# M-LVDS_PHY.net
KiCad netlist of a schematic drawn in Altium Designer
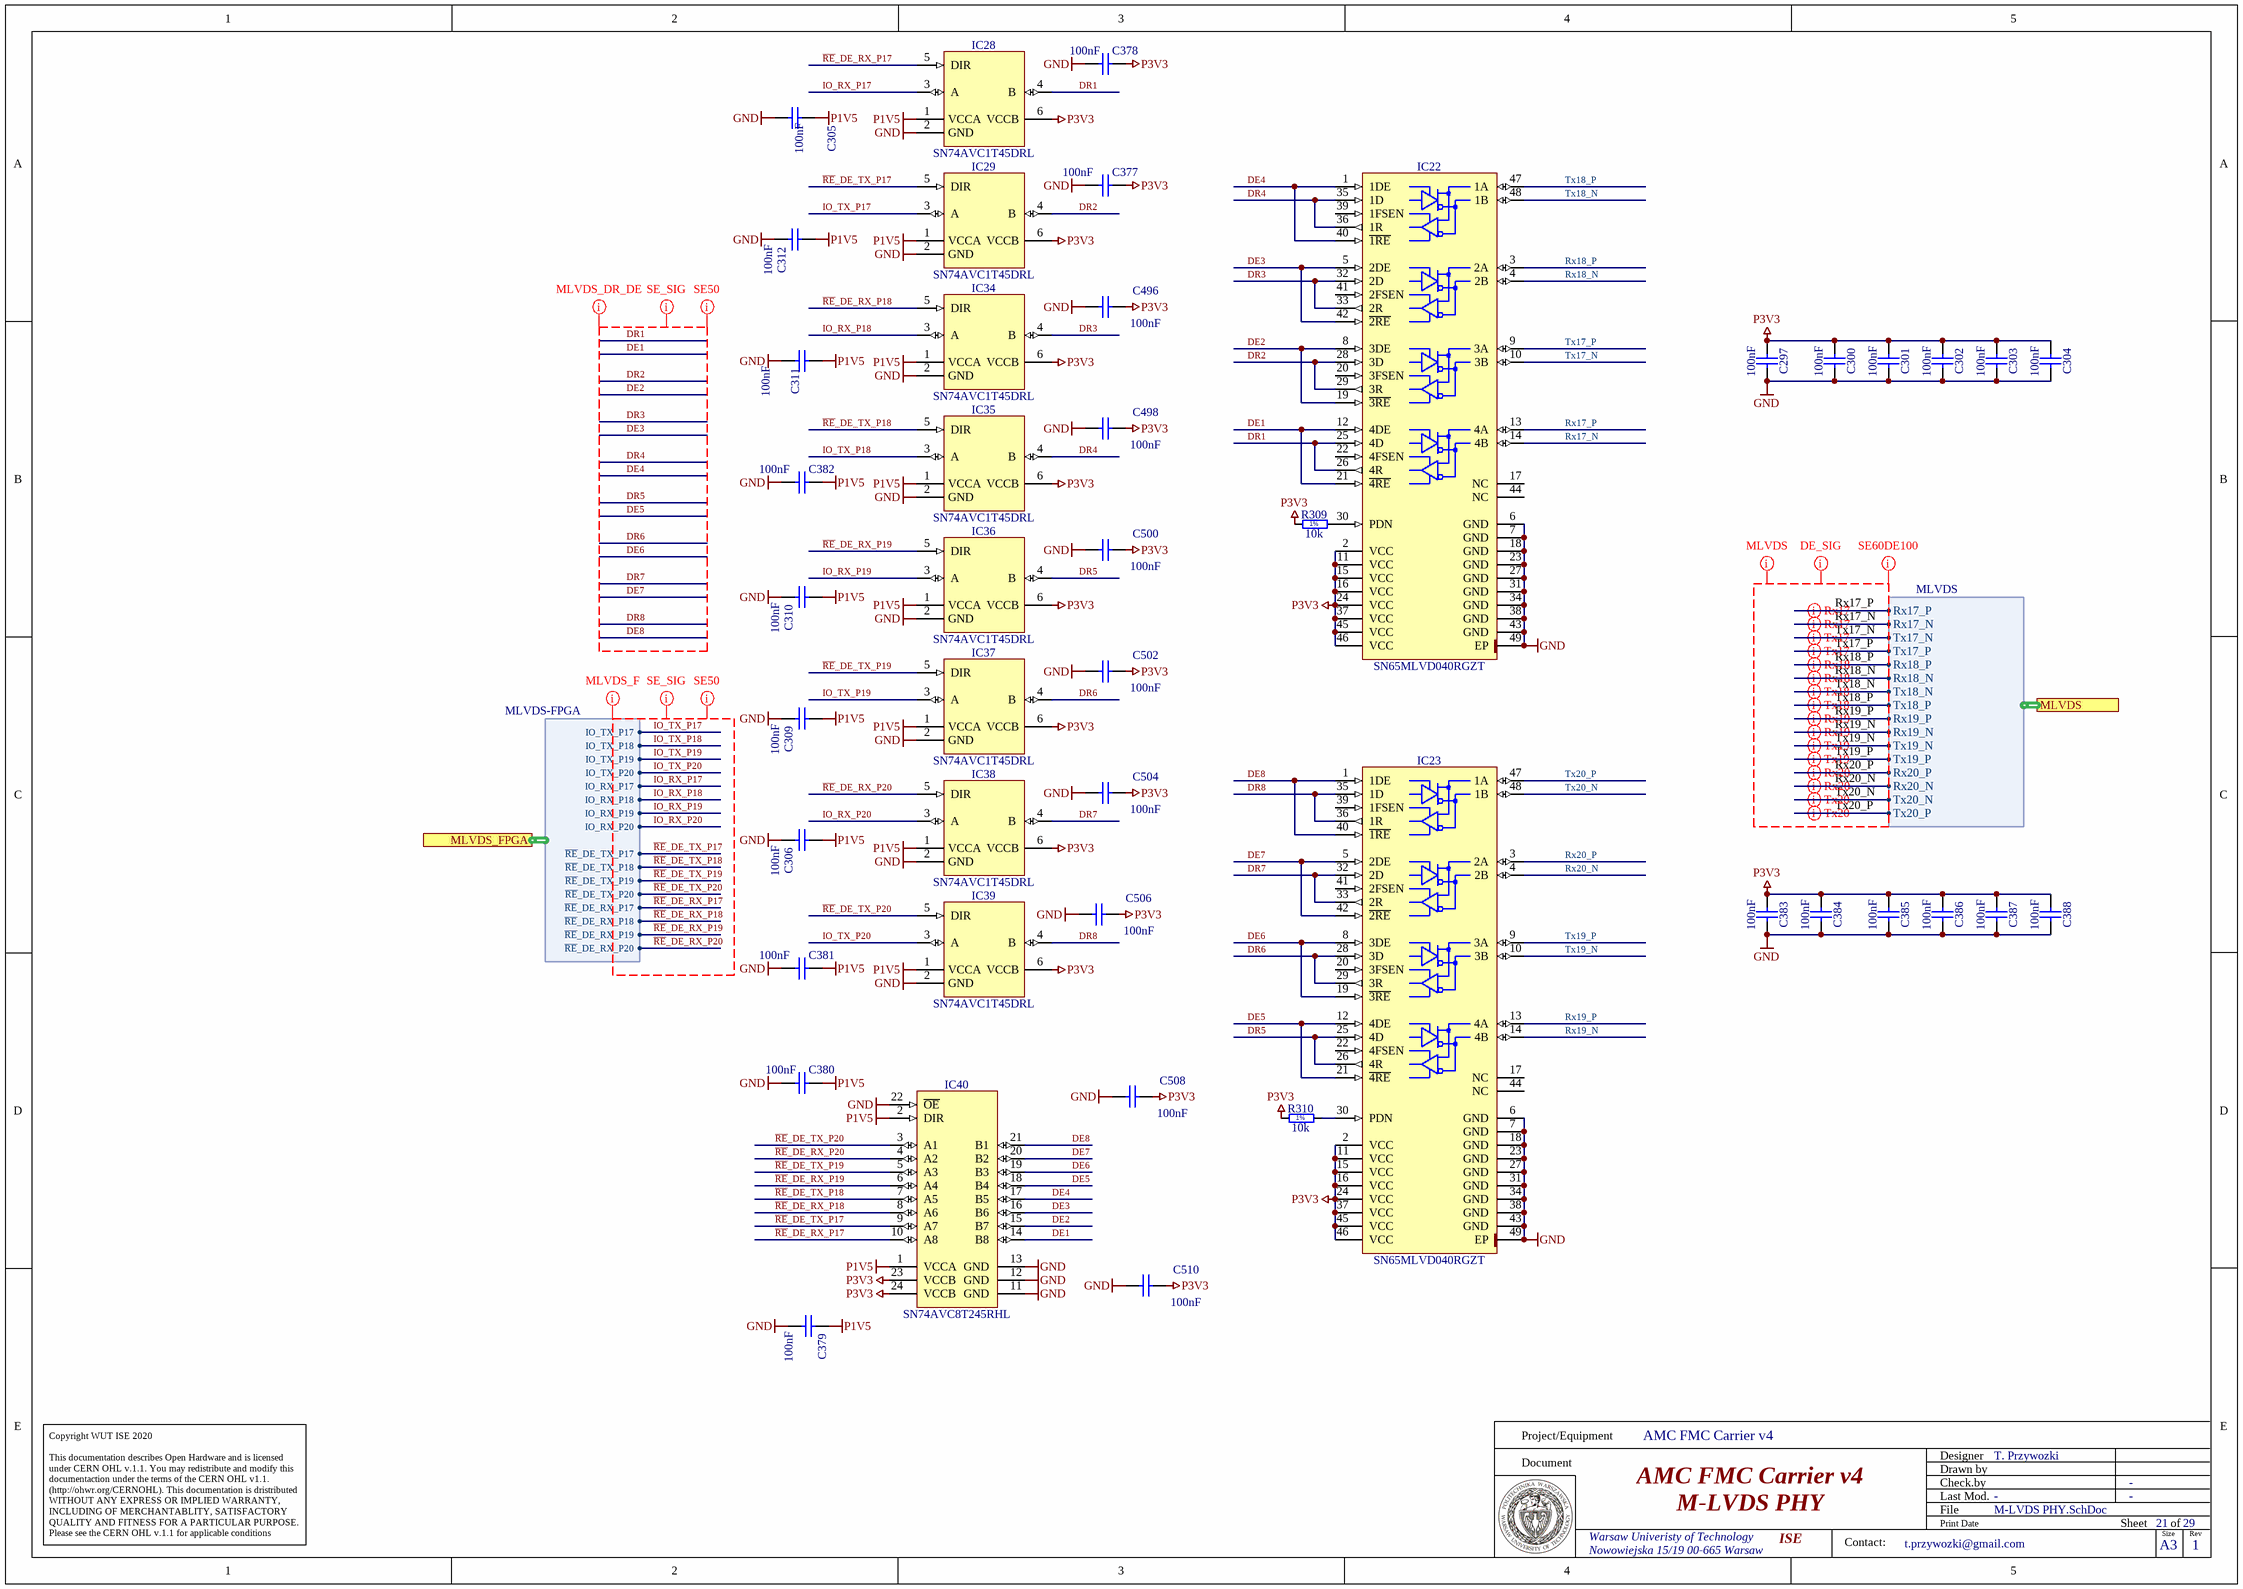
[diagram p0: M-LVDS PHY.SchDoc]

(export (version "E")
  (design (tool "Eeschema 10.0.6"))
  (components
    (comp (ref "C297")
      (value "100nF")
      (footprint "CAPC0603X33N")
      (description "Non-polarised capacitor")
      (fields
        (field (name "PART NUMBER") "CC0201_100NF_6.3V_10%_X5R")
        (field (name "VOLTAGE") "6.3V")
        (field (name "AUTHOR") "CERN DEM JLC")
      )
      (libsource (lib "Capacitors") (part "Capacitor - non polarized"))
    )
    (comp (ref "C300")
      (value "100nF")
      (footprint "CAPC0603X33N")
      (description "Non-polarised capacitor")
      (fields
        (field (name "PART NUMBER") "CC0201_100NF_6.3V_10%_X5R")
        (field (name "VOLTAGE") "6.3V")
        (field (name "AUTHOR") "CERN DEM JLC")
      )
      (libsource (lib "Capacitors") (part "Capacitor - non polarized"))
    )
    (comp (ref "C301")
      (value "100nF")
      (footprint "CAPC0603X33N")
      (description "Non-polarised capacitor")
      (fields
        (field (name "PART NUMBER") "CC0201_100NF_6.3V_10%_X5R")
        (field (name "VOLTAGE") "6.3V")
        (field (name "AUTHOR") "CERN DEM JLC")
      )
      (libsource (lib "Capacitors") (part "Capacitor - non polarized"))
    )
    (comp (ref "C302")
      (value "100nF")
      (footprint "CAPC0603X33N")
      (description "Non-polarised capacitor")
      (fields
        (field (name "PART NUMBER") "CC0201_100NF_6.3V_10%_X5R")
        (field (name "VOLTAGE") "6.3V")
        (field (name "AUTHOR") "CERN DEM JLC")
      )
      (libsource (lib "Capacitors") (part "Capacitor - non polarized"))
    )
    (comp (ref "C303")
      (value "100nF")
      (footprint "CAPC0603X33N")
      (description "Non-polarised capacitor")
      (fields
        (field (name "PART NUMBER") "CC0201_100NF_6.3V_10%_X5R")
        (field (name "VOLTAGE") "6.3V")
        (field (name "AUTHOR") "CERN DEM JLC")
      )
      (libsource (lib "Capacitors") (part "Capacitor - non polarized"))
    )
    (comp (ref "C304")
      (value "100nF")
      (footprint "CAPC0603X33N")
      (description "Non-polarised capacitor")
      (fields
        (field (name "PART NUMBER") "CC0201_100NF_6.3V_10%_X5R")
        (field (name "VOLTAGE") "6.3V")
        (field (name "AUTHOR") "CERN DEM JLC")
      )
      (libsource (lib "Capacitors") (part "Capacitor - non polarized"))
    )
    (comp (ref "C305")
      (value "100nF")
      (footprint "CAPC0603X33N")
      (description "Non-polarised capacitor")
      (fields
        (field (name "PART NUMBER") "CC0201_100NF_6.3V_10%_X5R")
        (field (name "VOLTAGE") "6.3V")
        (field (name "AUTHOR") "CERN DEM JLC")
      )
      (libsource (lib "Capacitors") (part "Capacitor - non polarized"))
    )
    (comp (ref "C306")
      (value "100nF")
      (footprint "CAPC0603X33N")
      (description "Non-polarised capacitor")
      (fields
        (field (name "PART NUMBER") "CC0201_100NF_6.3V_10%_X5R")
        (field (name "VOLTAGE") "6.3V")
        (field (name "AUTHOR") "CERN DEM JLC")
      )
      (libsource (lib "Capacitors") (part "Capacitor - non polarized"))
    )
    (comp (ref "C309")
      (value "100nF")
      (footprint "CAPC0603X33N")
      (description "Non-polarised capacitor")
      (fields
        (field (name "PART NUMBER") "CC0201_100NF_6.3V_10%_X5R")
        (field (name "VOLTAGE") "6.3V")
        (field (name "AUTHOR") "CERN DEM JLC")
      )
      (libsource (lib "Capacitors") (part "Capacitor - non polarized"))
    )
    (comp (ref "C310")
      (value "100nF")
      (footprint "CAPC0603X33N")
      (description "Non-polarised capacitor")
      (fields
        (field (name "PART NUMBER") "CC0201_100NF_6.3V_10%_X5R")
        (field (name "VOLTAGE") "6.3V")
        (field (name "AUTHOR") "CERN DEM JLC")
      )
      (libsource (lib "Capacitors") (part "Capacitor - non polarized"))
    )
    (comp (ref "C311")
      (value "100nF")
      (footprint "CAPC0603X33N")
      (description "Non-polarised capacitor")
      (fields
        (field (name "PART NUMBER") "CC0201_100NF_6.3V_10%_X5R")
        (field (name "VOLTAGE") "6.3V")
        (field (name "AUTHOR") "CERN DEM JLC")
      )
      (libsource (lib "Capacitors") (part "Capacitor - non polarized"))
    )
    (comp (ref "C312")
      (value "100nF")
      (footprint "CAPC0603X33N")
      (description "Non-polarised capacitor")
      (fields
        (field (name "PART NUMBER") "CC0201_100NF_6.3V_10%_X5R")
        (field (name "VOLTAGE") "6.3V")
        (field (name "AUTHOR") "CERN DEM JLC")
      )
      (libsource (lib "Capacitors") (part "Capacitor - non polarized"))
    )
    (comp (ref "C377")
      (value "100nF")
      (footprint "CAPC0603X33N")
      (description "Non-polarised capacitor")
      (fields
        (field (name "PART NUMBER") "CC0201_100NF_6.3V_10%_X5R")
        (field (name "VOLTAGE") "6.3V")
        (field (name "AUTHOR") "CERN DEM JLC")
      )
      (libsource (lib "Capacitors") (part "Capacitor - non polarized"))
    )
    (comp (ref "C378")
      (value "100nF")
      (footprint "CAPC0603X33N")
      (description "Non-polarised capacitor")
      (fields
        (field (name "PART NUMBER") "CC0201_100NF_6.3V_10%_X5R")
        (field (name "VOLTAGE") "6.3V")
        (field (name "AUTHOR") "CERN DEM JLC")
      )
      (libsource (lib "Capacitors") (part "Capacitor - non polarized"))
    )
    (comp (ref "C379")
      (value "100nF")
      (footprint "CAPC0603X33N")
      (description "Non-polarised capacitor")
      (fields
        (field (name "PART NUMBER") "CC0201_100NF_6.3V_10%_X5R")
        (field (name "VOLTAGE") "6.3V")
        (field (name "AUTHOR") "CERN DEM JLC")
      )
      (libsource (lib "Capacitors") (part "Capacitor - non polarized"))
    )
    (comp (ref "C380")
      (value "100nF")
      (footprint "CAPC0603X33N")
      (description "Non-polarised capacitor")
      (fields
        (field (name "PART NUMBER") "CC0201_100NF_6.3V_10%_X5R")
        (field (name "VOLTAGE") "6.3V")
        (field (name "AUTHOR") "CERN DEM JLC")
      )
      (libsource (lib "Capacitors") (part "Capacitor - non polarized"))
    )
    (comp (ref "C381")
      (value "100nF")
      (footprint "CAPC0603X33N")
      (description "Non-polarised capacitor")
      (fields
        (field (name "PART NUMBER") "CC0201_100NF_6.3V_10%_X5R")
        (field (name "VOLTAGE") "6.3V")
        (field (name "AUTHOR") "CERN DEM JLC")
      )
      (libsource (lib "Capacitors") (part "Capacitor - non polarized"))
    )
    (comp (ref "C382")
      (value "100nF")
      (footprint "CAPC0603X33N")
      (description "Non-polarised capacitor")
      (fields
        (field (name "PART NUMBER") "CC0201_100NF_6.3V_10%_X5R")
        (field (name "VOLTAGE") "6.3V")
        (field (name "AUTHOR") "CERN DEM JLC")
      )
      (libsource (lib "Capacitors") (part "Capacitor - non polarized"))
    )
    (comp (ref "C383")
      (value "100nF")
      (footprint "CAPC0603X33N")
      (description "Non-polarised capacitor")
      (fields
        (field (name "PART NUMBER") "CC0201_100NF_6.3V_10%_X5R")
        (field (name "VOLTAGE") "6.3V")
        (field (name "AUTHOR") "CERN DEM JLC")
      )
      (libsource (lib "Capacitors") (part "Capacitor - non polarized"))
    )
    (comp (ref "C384")
      (value "100nF")
      (footprint "CAPC0603X33N")
      (description "Non-polarised capacitor")
      (fields
        (field (name "PART NUMBER") "CC0201_100NF_6.3V_10%_X5R")
        (field (name "VOLTAGE") "6.3V")
        (field (name "AUTHOR") "CERN DEM JLC")
      )
      (libsource (lib "Capacitors") (part "Capacitor - non polarized"))
    )
    (comp (ref "C385")
      (value "100nF")
      (footprint "CAPC0603X33N")
      (description "Non-polarised capacitor")
      (fields
        (field (name "PART NUMBER") "CC0201_100NF_6.3V_10%_X5R")
        (field (name "VOLTAGE") "6.3V")
        (field (name "AUTHOR") "CERN DEM JLC")
      )
      (libsource (lib "Capacitors") (part "Capacitor - non polarized"))
    )
    (comp (ref "C386")
      (value "100nF")
      (footprint "CAPC0603X33N")
      (description "Non-polarised capacitor")
      (fields
        (field (name "PART NUMBER") "CC0201_100NF_6.3V_10%_X5R")
        (field (name "VOLTAGE") "6.3V")
        (field (name "AUTHOR") "CERN DEM JLC")
      )
      (libsource (lib "Capacitors") (part "Capacitor - non polarized"))
    )
    (comp (ref "C387")
      (value "100nF")
      (footprint "CAPC0603X33N")
      (description "Non-polarised capacitor")
      (fields
        (field (name "PART NUMBER") "CC0201_100NF_6.3V_10%_X5R")
        (field (name "VOLTAGE") "6.3V")
        (field (name "AUTHOR") "CERN DEM JLC")
      )
      (libsource (lib "Capacitors") (part "Capacitor - non polarized"))
    )
    (comp (ref "C388")
      (value "100nF")
      (footprint "CAPC0603X33N")
      (description "Non-polarised capacitor")
      (fields
        (field (name "PART NUMBER") "CC0201_100NF_6.3V_10%_X5R")
        (field (name "VOLTAGE") "6.3V")
        (field (name "AUTHOR") "CERN DEM JLC")
      )
      (libsource (lib "Capacitors") (part "Capacitor - non polarized"))
    )
    (comp (ref "C496")
      (value "100nF")
      (footprint "CAPC0603X33N")
      (description "Non-polarised capacitor")
      (fields
        (field (name "PART NUMBER") "CC0201_100NF_6.3V_10%_X5R")
        (field (name "VOLTAGE") "6.3V")
        (field (name "AUTHOR") "CERN DEM JLC")
      )
      (libsource (lib "Capacitors") (part "Capacitor - non polarized"))
    )
    (comp (ref "C498")
      (value "100nF")
      (footprint "CAPC0603X33N")
      (description "Non-polarised capacitor")
      (fields
        (field (name "PART NUMBER") "CC0201_100NF_6.3V_10%_X5R")
        (field (name "VOLTAGE") "6.3V")
        (field (name "AUTHOR") "CERN DEM JLC")
      )
      (libsource (lib "Capacitors") (part "Capacitor - non polarized"))
    )
    (comp (ref "C500")
      (value "100nF")
      (footprint "CAPC0603X33N")
      (description "Non-polarised capacitor")
      (fields
        (field (name "PART NUMBER") "CC0201_100NF_6.3V_10%_X5R")
        (field (name "VOLTAGE") "6.3V")
        (field (name "AUTHOR") "CERN DEM JLC")
      )
      (libsource (lib "Capacitors") (part "Capacitor - non polarized"))
    )
    (comp (ref "C502")
      (value "100nF")
      (footprint "CAPC0603X33N")
      (description "Non-polarised capacitor")
      (fields
        (field (name "PART NUMBER") "CC0201_100NF_6.3V_10%_X5R")
        (field (name "VOLTAGE") "6.3V")
        (field (name "AUTHOR") "CERN DEM JLC")
      )
      (libsource (lib "Capacitors") (part "Capacitor - non polarized"))
    )
    (comp (ref "C504")
      (value "100nF")
      (footprint "CAPC0603X33N")
      (description "Non-polarised capacitor")
      (fields
        (field (name "PART NUMBER") "CC0201_100NF_6.3V_10%_X5R")
        (field (name "VOLTAGE") "6.3V")
        (field (name "AUTHOR") "CERN DEM JLC")
      )
      (libsource (lib "Capacitors") (part "Capacitor - non polarized"))
    )
    (comp (ref "C506")
      (value "100nF")
      (footprint "CAPC0603X33N")
      (description "Non-polarised capacitor")
      (fields
        (field (name "PART NUMBER") "CC0201_100NF_6.3V_10%_X5R")
        (field (name "VOLTAGE") "6.3V")
        (field (name "AUTHOR") "CERN DEM JLC")
      )
      (libsource (lib "Capacitors") (part "Capacitor - non polarized"))
    )
    (comp (ref "C508")
      (value "100nF")
      (footprint "CAPC0603X33N")
      (description "Non-polarised capacitor")
      (fields
        (field (name "PART NUMBER") "CC0201_100NF_6.3V_10%_X5R")
        (field (name "VOLTAGE") "6.3V")
        (field (name "AUTHOR") "CERN DEM JLC")
      )
      (libsource (lib "Capacitors") (part "Capacitor - non polarized"))
    )
    (comp (ref "C510")
      (value "100nF")
      (footprint "CAPC0603X33N")
      (description "Non-polarised capacitor")
      (fields
        (field (name "PART NUMBER") "CC0201_100NF_6.3V_10%_X5R")
        (field (name "VOLTAGE") "6.3V")
        (field (name "AUTHOR") "CERN DEM JLC")
      )
      (libsource (lib "Capacitors") (part "Capacitor - non polarized"))
    )
    (comp (ref "IC22")
      (value "SN65MLVD040RGZT")
      (footprint "QFN50P700X700X100-49N-S420")
      (description "4-Channel Half-Duplex M-LVDS Line Transceiver")
      (fields (field (name "MANUFACTURER") "TEXAS INSTRUMENTS") (field (name "AUTHOR") "CERN DEM JLC"))
      (libsource (lib "ICs And Semiconductors") (part "SN65MLVD040"))
    )
    (comp (ref "IC23")
      (value "SN65MLVD040RGZT")
      (footprint "QFN50P700X700X100-49N-S420")
      (description "4-Channel Half-Duplex M-LVDS Line Transceiver")
      (fields (field (name "MANUFACTURER") "TEXAS INSTRUMENTS") (field (name "AUTHOR") "CERN DEM JLC"))
      (libsource (lib "ICs And Semiconductors") (part "SN65MLVD040"))
    )
    (comp (ref "IC28")
      (value "SN74AVC1T45DRL")
      (footprint "SOTFL50P160X60-6N")
      (description "Single-Bit Dual-Supply Bus Transceiver")
      (fields (field (name "MANUFACTURER") "TEXAS INSTRUMENTS") (field (name "AUTHOR") "CERN DEM MR"))
      (libsource (lib "ICs And Semiconductors") (part "741T45"))
    )
    (comp (ref "IC29")
      (value "SN74AVC1T45DRL")
      (footprint "SOTFL50P160X60-6N")
      (description "Single-Bit Dual-Supply Bus Transceiver")
      (fields (field (name "MANUFACTURER") "TEXAS INSTRUMENTS") (field (name "AUTHOR") "CERN DEM MR"))
      (libsource (lib "ICs And Semiconductors") (part "741T45"))
    )
    (comp (ref "IC34")
      (value "SN74AVC1T45DRL")
      (footprint "SOTFL50P160X60-6N")
      (description "Single-Bit Dual-Supply Bus Transceiver")
      (fields (field (name "MANUFACTURER") "TEXAS INSTRUMENTS") (field (name "AUTHOR") "CERN DEM MR"))
      (libsource (lib "ICs And Semiconductors") (part "741T45"))
    )
    (comp (ref "IC35")
      (value "SN74AVC1T45DRL")
      (footprint "SOTFL50P160X60-6N")
      (description "Single-Bit Dual-Supply Bus Transceiver")
      (fields (field (name "MANUFACTURER") "TEXAS INSTRUMENTS") (field (name "AUTHOR") "CERN DEM MR"))
      (libsource (lib "ICs And Semiconductors") (part "741T45"))
    )
    (comp (ref "IC36")
      (value "SN74AVC1T45DRL")
      (footprint "SOTFL50P160X60-6N")
      (description "Single-Bit Dual-Supply Bus Transceiver")
      (fields (field (name "MANUFACTURER") "TEXAS INSTRUMENTS") (field (name "AUTHOR") "CERN DEM MR"))
      (libsource (lib "ICs And Semiconductors") (part "741T45"))
    )
    (comp (ref "IC37")
      (value "SN74AVC1T45DRL")
      (footprint "SOTFL50P160X60-6N")
      (description "Single-Bit Dual-Supply Bus Transceiver")
      (fields (field (name "MANUFACTURER") "TEXAS INSTRUMENTS") (field (name "AUTHOR") "CERN DEM MR"))
      (libsource (lib "ICs And Semiconductors") (part "741T45"))
    )
    (comp (ref "IC38")
      (value "SN74AVC1T45DRL")
      (footprint "SOTFL50P160X60-6N")
      (description "Single-Bit Dual-Supply Bus Transceiver")
      (fields (field (name "MANUFACTURER") "TEXAS INSTRUMENTS") (field (name "AUTHOR") "CERN DEM MR"))
      (libsource (lib "ICs And Semiconductors") (part "741T45"))
    )
    (comp (ref "IC39")
      (value "SN74AVC1T45DRL")
      (footprint "SOTFL50P160X60-6N")
      (description "Single-Bit Dual-Supply Bus Transceiver")
      (fields (field (name "MANUFACTURER") "TEXAS INSTRUMENTS") (field (name "AUTHOR") "CERN DEM MR"))
      (libsource (lib "ICs And Semiconductors") (part "741T45"))
    )
    (comp (ref "IC40")
      (value "SN74AVC8T245RHL")
      (footprint "TEXAS_RHL (S-PVQFN-N24)")
      (description "8-Bit Dual-Supply Bus Transceiver With Configurable Voltage Translation and 3-State Outputs")
      (fields (field (name "MANUFACTURER") "TEXAS INSTRUMENTS") (field (name "AUTHOR") "CERN DEM MR"))
      (libsource (lib "ICs And Semiconductors") (part "748T245"))
    )
    (comp (ref "R309")
      (value "10k")
      (footprint "RESC1005X40N")
      (description "Resistor - 1%")
      (fields
        (field (name "PART NUMBER") "R0402_10K_1%_0.0625W_100PPM")
        (field (name "POWER") "0.0625W")
        (field (name "AUTHOR") "CERN DEM JLC")
      )
      (libsource (lib "Resistors") (part "Resistor - 1%"))
    )
    (comp (ref "R310")
      (value "10k")
      (footprint "RESC1005X40N")
      (description "Resistor - 1%")
      (fields
        (field (name "PART NUMBER") "R0402_10K_1%_0.0625W_100PPM")
        (field (name "POWER") "0.0625W")
        (field (name "AUTHOR") "CERN DEM JLC")
      )
      (libsource (lib "Resistors") (part "Resistor - 1%"))
    )
  )
  (nets
    (net (code "3") (name "/DE1") (class "Default")
      (node (ref "IC22") (pin "12") (pinfunction "4DE_12") (pintype "input"))
      (node (ref "IC22") (pin "21") (pinfunction "~{4RE}_21") (pintype "input"))
      (node (ref "IC40") (pin "14") (pinfunction "B8_14") (pintype "bidirectional"))
    )
    (net (code "4") (name "/DE2") (class "Default")
      (node (ref "IC22") (pin "19") (pinfunction "~{3RE}_19") (pintype "input"))
      (node (ref "IC22") (pin "8") (pinfunction "3DE_8") (pintype "input"))
      (node (ref "IC40") (pin "15") (pinfunction "B7_15") (pintype "bidirectional"))
    )
    (net (code "5") (name "/DE3") (class "Default")
      (node (ref "IC22") (pin "42") (pinfunction "~{2RE}_42") (pintype "input"))
      (node (ref "IC22") (pin "5") (pinfunction "2DE_5") (pintype "input"))
      (node (ref "IC40") (pin "16") (pinfunction "B6_16") (pintype "bidirectional"))
    )
    (net (code "6") (name "/DE4") (class "Default")
      (node (ref "IC22") (pin "1") (pinfunction "1DE_1") (pintype "input"))
      (node (ref "IC22") (pin "40") (pinfunction "~{1RE}_40") (pintype "input"))
      (node (ref "IC40") (pin "17") (pinfunction "B5_17") (pintype "bidirectional"))
    )
    (net (code "7") (name "/DE5") (class "Default")
      (node (ref "IC23") (pin "12") (pinfunction "4DE_12") (pintype "input"))
      (node (ref "IC23") (pin "21") (pinfunction "~{4RE}_21") (pintype "input"))
      (node (ref "IC40") (pin "18") (pinfunction "B4_18") (pintype "bidirectional"))
    )
    (net (code "8") (name "/DE6") (class "Default")
      (node (ref "IC23") (pin "19") (pinfunction "~{3RE}_19") (pintype "input"))
      (node (ref "IC23") (pin "8") (pinfunction "3DE_8") (pintype "input"))
      (node (ref "IC40") (pin "19") (pinfunction "B3_19") (pintype "bidirectional"))
    )
    (net (code "9") (name "/DE7") (class "Default")
      (node (ref "IC23") (pin "42") (pinfunction "~{2RE}_42") (pintype "input"))
      (node (ref "IC23") (pin "5") (pinfunction "2DE_5") (pintype "input"))
      (node (ref "IC40") (pin "20") (pinfunction "B2_20") (pintype "bidirectional"))
    )
    (net (code "10") (name "/DE8") (class "Default")
      (node (ref "IC23") (pin "1") (pinfunction "1DE_1") (pintype "input"))
      (node (ref "IC23") (pin "40") (pinfunction "~{1RE}_40") (pintype "input"))
      (node (ref "IC40") (pin "21") (pinfunction "B1_21") (pintype "bidirectional"))
    )
    (net (code "11") (name "/DR1") (class "Default")
      (node (ref "IC22") (pin "25") (pinfunction "4D_25") (pintype "input"))
      (node (ref "IC22") (pin "26") (pinfunction "4R_26") (pintype "output"))
      (node (ref "IC28") (pin "4") (pinfunction "B_4") (pintype "bidirectional"))
    )
    (net (code "12") (name "/DR2") (class "Default")
      (node (ref "IC22") (pin "28") (pinfunction "3D_28") (pintype "input"))
      (node (ref "IC22") (pin "29") (pinfunction "3R_29") (pintype "output"))
      (node (ref "IC29") (pin "4") (pinfunction "B_4") (pintype "bidirectional"))
    )
    (net (code "13") (name "/DR3") (class "Default")
      (node (ref "IC22") (pin "32") (pinfunction "2D_32") (pintype "input"))
      (node (ref "IC22") (pin "33") (pinfunction "2R_33") (pintype "output"))
      (node (ref "IC34") (pin "4") (pinfunction "B_4") (pintype "bidirectional"))
    )
    (net (code "14") (name "/DR4") (class "Default")
      (node (ref "IC22") (pin "35") (pinfunction "1D_35") (pintype "input"))
      (node (ref "IC22") (pin "36") (pinfunction "1R_36") (pintype "output"))
      (node (ref "IC35") (pin "4") (pinfunction "B_4") (pintype "bidirectional"))
    )
    (net (code "15") (name "/DR5") (class "Default")
      (node (ref "IC23") (pin "25") (pinfunction "4D_25") (pintype "input"))
      (node (ref "IC23") (pin "26") (pinfunction "4R_26") (pintype "output"))
      (node (ref "IC36") (pin "4") (pinfunction "B_4") (pintype "bidirectional"))
    )
    (net (code "16") (name "/DR6") (class "Default")
      (node (ref "IC23") (pin "28") (pinfunction "3D_28") (pintype "input"))
      (node (ref "IC23") (pin "29") (pinfunction "3R_29") (pintype "output"))
      (node (ref "IC37") (pin "4") (pinfunction "B_4") (pintype "bidirectional"))
    )
    (net (code "17") (name "/DR7") (class "Default")
      (node (ref "IC23") (pin "32") (pinfunction "2D_32") (pintype "input"))
      (node (ref "IC23") (pin "33") (pinfunction "2R_33") (pintype "output"))
      (node (ref "IC38") (pin "4") (pinfunction "B_4") (pintype "bidirectional"))
    )
    (net (code "18") (name "/DR8") (class "Default")
      (node (ref "IC23") (pin "35") (pinfunction "1D_35") (pintype "input"))
      (node (ref "IC23") (pin "36") (pinfunction "1R_36") (pintype "output"))
      (node (ref "IC39") (pin "4") (pinfunction "B_4") (pintype "bidirectional"))
    )
    (net (code "19") (name "/IO_RX_P17") (class "Default")
      (node (ref "IC28") (pin "3") (pinfunction "A_3") (pintype "bidirectional"))
    )
    (net (code "20") (name "/IO_RX_P18") (class "Default")
      (node (ref "IC34") (pin "3") (pinfunction "A_3") (pintype "bidirectional"))
    )
    (net (code "21") (name "/IO_RX_P19") (class "Default")
      (node (ref "IC36") (pin "3") (pinfunction "A_3") (pintype "bidirectional"))
    )
    (net (code "22") (name "/IO_RX_P20") (class "Default")
      (node (ref "IC38") (pin "3") (pinfunction "A_3") (pintype "bidirectional"))
    )
    (net (code "23") (name "/IO_TX_P17") (class "Default")
      (node (ref "IC29") (pin "3") (pinfunction "A_3") (pintype "bidirectional"))
    )
    (net (code "24") (name "/IO_TX_P18") (class "Default")
      (node (ref "IC35") (pin "3") (pinfunction "A_3") (pintype "bidirectional"))
    )
    (net (code "25") (name "/IO_TX_P19") (class "Default")
      (node (ref "IC37") (pin "3") (pinfunction "A_3") (pintype "bidirectional"))
    )
    (net (code "26") (name "/IO_TX_P20") (class "Default")
      (node (ref "IC39") (pin "3") (pinfunction "A_3") (pintype "bidirectional"))
    )
    (net (code "27") (name "/Rx17_N") (class "Default")
      (node (ref "IC22") (pin "14") (pinfunction "4B_14") (pintype "bidirectional"))
    )
    (net (code "28") (name "/Rx17_P") (class "Default")
      (node (ref "IC22") (pin "13") (pinfunction "4A_13") (pintype "bidirectional"))
    )
    (net (code "29") (name "/Rx18_N") (class "Default")
      (node (ref "IC22") (pin "4") (pinfunction "2B_4") (pintype "bidirectional"))
    )
    (net (code "30") (name "/Rx18_P") (class "Default")
      (node (ref "IC22") (pin "3") (pinfunction "2A_3") (pintype "bidirectional"))
    )
    (net (code "31") (name "/Rx19_N") (class "Default")
      (node (ref "IC23") (pin "14") (pinfunction "4B_14") (pintype "bidirectional"))
    )
    (net (code "32") (name "/Rx19_P") (class "Default")
      (node (ref "IC23") (pin "13") (pinfunction "4A_13") (pintype "bidirectional"))
    )
    (net (code "33") (name "/Rx20_N") (class "Default")
      (node (ref "IC23") (pin "4") (pinfunction "2B_4") (pintype "bidirectional"))
    )
    (net (code "34") (name "/Rx20_P") (class "Default")
      (node (ref "IC23") (pin "3") (pinfunction "2A_3") (pintype "bidirectional"))
    )
    (net (code "35") (name "/Tx17_N") (class "Default")
      (node (ref "IC22") (pin "10") (pinfunction "3B_10") (pintype "bidirectional"))
    )
    (net (code "36") (name "/Tx17_P") (class "Default")
      (node (ref "IC22") (pin "9") (pinfunction "3A_9") (pintype "bidirectional"))
    )
    (net (code "37") (name "/Tx18_N") (class "Default")
      (node (ref "IC22") (pin "48") (pinfunction "1B_48") (pintype "bidirectional"))
    )
    (net (code "38") (name "/Tx18_P") (class "Default")
      (node (ref "IC22") (pin "47") (pinfunction "1A_47") (pintype "bidirectional"))
    )
    (net (code "39") (name "/Tx19_N") (class "Default")
      (node (ref "IC23") (pin "10") (pinfunction "3B_10") (pintype "bidirectional"))
    )
    (net (code "40") (name "/Tx19_P") (class "Default")
      (node (ref "IC23") (pin "9") (pinfunction "3A_9") (pintype "bidirectional"))
    )
    (net (code "41") (name "/Tx20_N") (class "Default")
      (node (ref "IC23") (pin "48") (pinfunction "1B_48") (pintype "bidirectional"))
    )
    (net (code "42") (name "/Tx20_P") (class "Default")
      (node (ref "IC23") (pin "47") (pinfunction "1A_47") (pintype "bidirectional"))
    )
    (net (code "45") (name "/~{RE}_DE_RX_P17") (class "Default")
      (node (ref "IC28") (pin "5") (pinfunction "DIR_5") (pintype "input"))
      (node (ref "IC40") (pin "10") (pinfunction "A8_10") (pintype "bidirectional"))
    )
    (net (code "46") (name "/~{RE}_DE_RX_P18") (class "Default")
      (node (ref "IC34") (pin "5") (pinfunction "DIR_5") (pintype "input"))
      (node (ref "IC40") (pin "8") (pinfunction "A6_8") (pintype "bidirectional"))
    )
    (net (code "47") (name "/~{RE}_DE_RX_P19") (class "Default")
      (node (ref "IC36") (pin "5") (pinfunction "DIR_5") (pintype "input"))
      (node (ref "IC40") (pin "6") (pinfunction "A4_6") (pintype "bidirectional"))
    )
    (net (code "48") (name "/~{RE}_DE_RX_P20") (class "Default")
      (node (ref "IC38") (pin "5") (pinfunction "DIR_5") (pintype "input"))
      (node (ref "IC40") (pin "4") (pinfunction "A2_4") (pintype "bidirectional"))
    )
    (net (code "49") (name "/~{RE}_DE_TX_P17") (class "Default")
      (node (ref "IC29") (pin "5") (pinfunction "DIR_5") (pintype "input"))
      (node (ref "IC40") (pin "9") (pinfunction "A7_9") (pintype "bidirectional"))
    )
    (net (code "50") (name "/~{RE}_DE_TX_P18") (class "Default")
      (node (ref "IC35") (pin "5") (pinfunction "DIR_5") (pintype "input"))
      (node (ref "IC40") (pin "7") (pinfunction "A5_7") (pintype "bidirectional"))
    )
    (net (code "51") (name "/~{RE}_DE_TX_P19") (class "Default")
      (node (ref "IC37") (pin "5") (pinfunction "DIR_5") (pintype "input"))
      (node (ref "IC40") (pin "5") (pinfunction "A3_5") (pintype "bidirectional"))
    )
    (net (code "52") (name "/~{RE}_DE_TX_P20") (class "Default")
      (node (ref "IC39") (pin "5") (pinfunction "DIR_5") (pintype "input"))
      (node (ref "IC40") (pin "3") (pinfunction "A1_3") (pintype "bidirectional"))
    )
    (net (code "53") (name "GND") (class "Default")
      (node (ref "C297") (pin "2") (pinfunction "2_2") (pintype "passive"))
      (node (ref "C300") (pin "2") (pinfunction "2_2") (pintype "passive"))
      (node (ref "C301") (pin "2") (pinfunction "2_2") (pintype "passive"))
      (node (ref "C302") (pin "2") (pinfunction "2_2") (pintype "passive"))
      (node (ref "C303") (pin "2") (pinfunction "2_2") (pintype "passive"))
      (node (ref "C304") (pin "2") (pinfunction "2_2") (pintype "passive"))
      (node (ref "C305") (pin "2") (pinfunction "2_2") (pintype "passive"))
      (node (ref "C306") (pin "1") (pinfunction "1_1") (pintype "passive"))
      (node (ref "C309") (pin "1") (pinfunction "1_1") (pintype "passive"))
      (node (ref "C310") (pin "1") (pinfunction "1_1") (pintype "passive"))
      (node (ref "C311") (pin "1") (pinfunction "1_1") (pintype "passive"))
      (node (ref "C312") (pin "1") (pinfunction "1_1") (pintype "passive"))
      (node (ref "C377") (pin "1") (pinfunction "1_1") (pintype "passive"))
      (node (ref "C378") (pin "1") (pinfunction "1_1") (pintype "passive"))
      (node (ref "C379") (pin "1") (pinfunction "1_1") (pintype "passive"))
      (node (ref "C380") (pin "1") (pinfunction "1_1") (pintype "passive"))
      (node (ref "C381") (pin "1") (pinfunction "1_1") (pintype "passive"))
      (node (ref "C382") (pin "1") (pinfunction "1_1") (pintype "passive"))
      (node (ref "C383") (pin "2") (pinfunction "2_2") (pintype "passive"))
      (node (ref "C384") (pin "2") (pinfunction "2_2") (pintype "passive"))
      (node (ref "C385") (pin "2") (pinfunction "2_2") (pintype "passive"))
      (node (ref "C386") (pin "2") (pinfunction "2_2") (pintype "passive"))
      (node (ref "C387") (pin "2") (pinfunction "2_2") (pintype "passive"))
      (node (ref "C388") (pin "2") (pinfunction "2_2") (pintype "passive"))
      (node (ref "C496") (pin "2") (pinfunction "2_2") (pintype "passive"))
      (node (ref "C498") (pin "2") (pinfunction "2_2") (pintype "passive"))
      (node (ref "C500") (pin "2") (pinfunction "2_2") (pintype "passive"))
      (node (ref "C502") (pin "2") (pinfunction "2_2") (pintype "passive"))
      (node (ref "C504") (pin "2") (pinfunction "2_2") (pintype "passive"))
      (node (ref "C506") (pin "2") (pinfunction "2_2") (pintype "passive"))
      (node (ref "C508") (pin "2") (pinfunction "2_2") (pintype "passive"))
      (node (ref "C510") (pin "2") (pinfunction "2_2") (pintype "passive"))
      (node (ref "IC22") (pin "18") (pinfunction "GND_18") (pintype "power_in"))
      (node (ref "IC22") (pin "23") (pinfunction "GND_23") (pintype "power_in"))
      (node (ref "IC22") (pin "27") (pinfunction "GND_27") (pintype "power_in"))
      (node (ref "IC22") (pin "31") (pinfunction "GND_31") (pintype "power_in"))
      (node (ref "IC22") (pin "34") (pinfunction "GND_34") (pintype "power_in"))
      (node (ref "IC22") (pin "38") (pinfunction "GND_38") (pintype "power_in"))
      (node (ref "IC22") (pin "43") (pinfunction "GND_43") (pintype "power_in"))
      (node (ref "IC22") (pin "49") (pinfunction "EP_49") (pintype "power_in"))
      (node (ref "IC22") (pin "6") (pinfunction "GND_6") (pintype "power_in"))
      (node (ref "IC22") (pin "7") (pinfunction "GND_7") (pintype "power_in"))
      (node (ref "IC23") (pin "18") (pinfunction "GND_18") (pintype "power_in"))
      (node (ref "IC23") (pin "23") (pinfunction "GND_23") (pintype "power_in"))
      (node (ref "IC23") (pin "27") (pinfunction "GND_27") (pintype "power_in"))
      (node (ref "IC23") (pin "31") (pinfunction "GND_31") (pintype "power_in"))
      (node (ref "IC23") (pin "34") (pinfunction "GND_34") (pintype "power_in"))
      (node (ref "IC23") (pin "38") (pinfunction "GND_38") (pintype "power_in"))
      (node (ref "IC23") (pin "43") (pinfunction "GND_43") (pintype "power_in"))
      (node (ref "IC23") (pin "49") (pinfunction "EP_49") (pintype "power_in"))
      (node (ref "IC23") (pin "6") (pinfunction "GND_6") (pintype "power_in"))
      (node (ref "IC23") (pin "7") (pinfunction "GND_7") (pintype "power_in"))
      (node (ref "IC28") (pin "2") (pinfunction "GND_2") (pintype "power_in"))
      (node (ref "IC29") (pin "2") (pinfunction "GND_2") (pintype "power_in"))
      (node (ref "IC34") (pin "2") (pinfunction "GND_2") (pintype "power_in"))
      (node (ref "IC35") (pin "2") (pinfunction "GND_2") (pintype "power_in"))
      (node (ref "IC36") (pin "2") (pinfunction "GND_2") (pintype "power_in"))
      (node (ref "IC37") (pin "2") (pinfunction "GND_2") (pintype "power_in"))
      (node (ref "IC38") (pin "2") (pinfunction "GND_2") (pintype "power_in"))
      (node (ref "IC39") (pin "2") (pinfunction "GND_2") (pintype "power_in"))
      (node (ref "IC40") (pin "11") (pinfunction "GND_11") (pintype "power_in"))
      (node (ref "IC40") (pin "12") (pinfunction "GND_12") (pintype "power_in"))
      (node (ref "IC40") (pin "13") (pinfunction "GND_13") (pintype "power_in"))
      (node (ref "IC40") (pin "22") (pinfunction "~{OE}_22") (pintype "input"))
    )
    (net (code "54") (name "Net-(IC22-PDN)") (class "Default")
      (node (ref "IC22") (pin "30") (pinfunction "PDN_30") (pintype "input"))
      (node (ref "R309") (pin "2") (pinfunction "2_2") (pintype "passive"))
    )
    (net (code "55") (name "Net-(IC23-PDN)") (class "Default")
      (node (ref "IC23") (pin "30") (pinfunction "PDN_30") (pintype "input"))
      (node (ref "R310") (pin "2") (pinfunction "2_2") (pintype "passive"))
    )
    (net (code "56") (name "P1V5") (class "Default")
      (node (ref "C305") (pin "1") (pinfunction "1_1") (pintype "passive"))
      (node (ref "C306") (pin "2") (pinfunction "2_2") (pintype "passive"))
      (node (ref "C309") (pin "2") (pinfunction "2_2") (pintype "passive"))
      (node (ref "C310") (pin "2") (pinfunction "2_2") (pintype "passive"))
      (node (ref "C311") (pin "2") (pinfunction "2_2") (pintype "passive"))
      (node (ref "C312") (pin "2") (pinfunction "2_2") (pintype "passive"))
      (node (ref "C379") (pin "2") (pinfunction "2_2") (pintype "passive"))
      (node (ref "C380") (pin "2") (pinfunction "2_2") (pintype "passive"))
      (node (ref "C381") (pin "2") (pinfunction "2_2") (pintype "passive"))
      (node (ref "C382") (pin "2") (pinfunction "2_2") (pintype "passive"))
      (node (ref "IC28") (pin "1") (pinfunction "VCCA_1") (pintype "power_in"))
      (node (ref "IC29") (pin "1") (pinfunction "VCCA_1") (pintype "power_in"))
      (node (ref "IC34") (pin "1") (pinfunction "VCCA_1") (pintype "power_in"))
      (node (ref "IC35") (pin "1") (pinfunction "VCCA_1") (pintype "power_in"))
      (node (ref "IC36") (pin "1") (pinfunction "VCCA_1") (pintype "power_in"))
      (node (ref "IC37") (pin "1") (pinfunction "VCCA_1") (pintype "power_in"))
      (node (ref "IC38") (pin "1") (pinfunction "VCCA_1") (pintype "power_in"))
      (node (ref "IC39") (pin "1") (pinfunction "VCCA_1") (pintype "power_in"))
      (node (ref "IC40") (pin "1") (pinfunction "VCCA_1") (pintype "power_in"))
      (node (ref "IC40") (pin "2") (pinfunction "DIR_2") (pintype "input"))
    )
    (net (code "57") (name "P3V3") (class "Default")
      (node (ref "C297") (pin "1") (pinfunction "1_1") (pintype "passive"))
      (node (ref "C300") (pin "1") (pinfunction "1_1") (pintype "passive"))
      (node (ref "C301") (pin "1") (pinfunction "1_1") (pintype "passive"))
      (node (ref "C302") (pin "1") (pinfunction "1_1") (pintype "passive"))
      (node (ref "C303") (pin "1") (pinfunction "1_1") (pintype "passive"))
      (node (ref "C304") (pin "1") (pinfunction "1_1") (pintype "passive"))
      (node (ref "C377") (pin "2") (pinfunction "2_2") (pintype "passive"))
      (node (ref "C378") (pin "2") (pinfunction "2_2") (pintype "passive"))
      (node (ref "C383") (pin "1") (pinfunction "1_1") (pintype "passive"))
      (node (ref "C384") (pin "1") (pinfunction "1_1") (pintype "passive"))
      (node (ref "C385") (pin "1") (pinfunction "1_1") (pintype "passive"))
      (node (ref "C386") (pin "1") (pinfunction "1_1") (pintype "passive"))
      (node (ref "C387") (pin "1") (pinfunction "1_1") (pintype "passive"))
      (node (ref "C388") (pin "1") (pinfunction "1_1") (pintype "passive"))
      (node (ref "C496") (pin "1") (pinfunction "1_1") (pintype "passive"))
      (node (ref "C498") (pin "1") (pinfunction "1_1") (pintype "passive"))
      (node (ref "C500") (pin "1") (pinfunction "1_1") (pintype "passive"))
      (node (ref "C502") (pin "1") (pinfunction "1_1") (pintype "passive"))
      (node (ref "C504") (pin "1") (pinfunction "1_1") (pintype "passive"))
      (node (ref "C506") (pin "1") (pinfunction "1_1") (pintype "passive"))
      (node (ref "C508") (pin "1") (pinfunction "1_1") (pintype "passive"))
      (node (ref "C510") (pin "1") (pinfunction "1_1") (pintype "passive"))
      (node (ref "IC22") (pin "11") (pinfunction "VCC_11") (pintype "power_in"))
      (node (ref "IC22") (pin "15") (pinfunction "VCC_15") (pintype "power_in"))
      (node (ref "IC22") (pin "16") (pinfunction "VCC_16") (pintype "power_in"))
      (node (ref "IC22") (pin "2") (pinfunction "VCC_2") (pintype "power_in"))
      (node (ref "IC22") (pin "24") (pinfunction "VCC_24") (pintype "power_in"))
      (node (ref "IC22") (pin "37") (pinfunction "VCC_37") (pintype "power_in"))
      (node (ref "IC22") (pin "45") (pinfunction "VCC_45") (pintype "power_in"))
      (node (ref "IC22") (pin "46") (pinfunction "VCC_46") (pintype "power_in"))
      (node (ref "IC23") (pin "11") (pinfunction "VCC_11") (pintype "power_in"))
      (node (ref "IC23") (pin "15") (pinfunction "VCC_15") (pintype "power_in"))
      (node (ref "IC23") (pin "16") (pinfunction "VCC_16") (pintype "power_in"))
      (node (ref "IC23") (pin "2") (pinfunction "VCC_2") (pintype "power_in"))
      (node (ref "IC23") (pin "24") (pinfunction "VCC_24") (pintype "power_in"))
      (node (ref "IC23") (pin "37") (pinfunction "VCC_37") (pintype "power_in"))
      (node (ref "IC23") (pin "45") (pinfunction "VCC_45") (pintype "power_in"))
      (node (ref "IC23") (pin "46") (pinfunction "VCC_46") (pintype "power_in"))
      (node (ref "IC28") (pin "6") (pinfunction "VCCB_6") (pintype "power_in"))
      (node (ref "IC29") (pin "6") (pinfunction "VCCB_6") (pintype "power_in"))
      (node (ref "IC34") (pin "6") (pinfunction "VCCB_6") (pintype "power_in"))
      (node (ref "IC35") (pin "6") (pinfunction "VCCB_6") (pintype "power_in"))
      (node (ref "IC36") (pin "6") (pinfunction "VCCB_6") (pintype "power_in"))
      (node (ref "IC37") (pin "6") (pinfunction "VCCB_6") (pintype "power_in"))
      (node (ref "IC38") (pin "6") (pinfunction "VCCB_6") (pintype "power_in"))
      (node (ref "IC39") (pin "6") (pinfunction "VCCB_6") (pintype "power_in"))
      (node (ref "IC40") (pin "23") (pinfunction "VCCB_23") (pintype "power_in"))
      (node (ref "IC40") (pin "24") (pinfunction "VCCB_24") (pintype "power_in"))
      (node (ref "R309") (pin "1") (pinfunction "1_1") (pintype "passive"))
      (node (ref "R310") (pin "1") (pinfunction "1_1") (pintype "passive"))
    )
    (net (code "58") (name "unconnected-(IC22-1FSEN-Pad39)") (class "Default")
      (node (ref "IC22") (pin "39") (pinfunction "1FSEN_39") (pintype "input"))
    )
    (net (code "59") (name "unconnected-(IC22-2FSEN-Pad41)") (class "Default")
      (node (ref "IC22") (pin "41") (pinfunction "2FSEN_41") (pintype "input"))
    )
    (net (code "60") (name "unconnected-(IC22-3FSEN-Pad20)") (class "Default")
      (node (ref "IC22") (pin "20") (pinfunction "3FSEN_20") (pintype "input"))
    )
    (net (code "61") (name "unconnected-(IC22-4FSEN-Pad22)") (class "Default")
      (node (ref "IC22") (pin "22") (pinfunction "4FSEN_22") (pintype "input"))
    )
    (net (code "62") (name "unconnected-(IC22-NC-Pad17)") (class "Default")
      (node (ref "IC22") (pin "17") (pinfunction "NC_17") (pintype "passive"))
    )
    (net (code "63") (name "unconnected-(IC22-NC-Pad44)") (class "Default")
      (node (ref "IC22") (pin "44") (pinfunction "NC_44") (pintype "passive"))
    )
    (net (code "64") (name "unconnected-(IC23-1FSEN-Pad39)") (class "Default")
      (node (ref "IC23") (pin "39") (pinfunction "1FSEN_39") (pintype "input"))
    )
    (net (code "65") (name "unconnected-(IC23-2FSEN-Pad41)") (class "Default")
      (node (ref "IC23") (pin "41") (pinfunction "2FSEN_41") (pintype "input"))
    )
    (net (code "66") (name "unconnected-(IC23-3FSEN-Pad20)") (class "Default")
      (node (ref "IC23") (pin "20") (pinfunction "3FSEN_20") (pintype "input"))
    )
    (net (code "67") (name "unconnected-(IC23-4FSEN-Pad22)") (class "Default")
      (node (ref "IC23") (pin "22") (pinfunction "4FSEN_22") (pintype "input"))
    )
    (net (code "68") (name "unconnected-(IC23-NC-Pad17)") (class "Default")
      (node (ref "IC23") (pin "17") (pinfunction "NC_17") (pintype "passive"))
    )
    (net (code "69") (name "unconnected-(IC23-NC-Pad44)") (class "Default")
      (node (ref "IC23") (pin "44") (pinfunction "NC_44") (pintype "passive"))
    )
  )
)
